# rectifiing.net
KiCad netlist of a schematic drawn in EAGLE
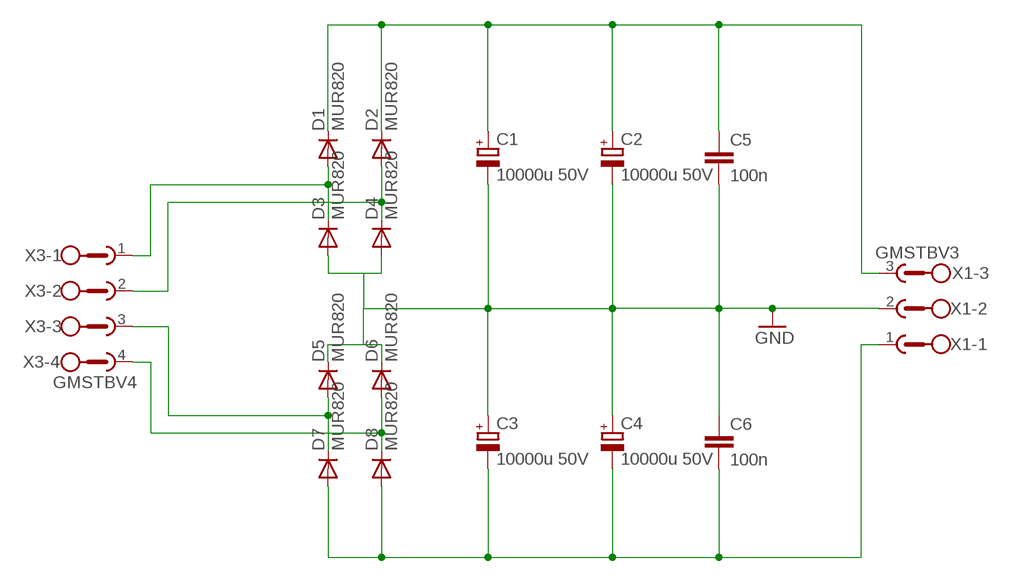
[diagram p0: schematic, sheet 1]

(export (version "E")
  (design (tool "Eeschema 10.0.6"))
  (components
    (comp (ref "C1")
      (value "10000u 50V")
      (footprint "eagle-import:EB30D")
      (libsource (lib "eagle-import") (part "CPOL-EUE10-30"))
    )
    (comp (ref "C2")
      (value "10000u 50V")
      (footprint "eagle-import:EB30D")
      (libsource (lib "eagle-import") (part "CPOL-EUE10-30"))
    )
    (comp (ref "C3")
      (value "10000u 50V")
      (footprint "eagle-import:EB30D")
      (libsource (lib "eagle-import") (part "CPOL-EUE10-30"))
    )
    (comp (ref "C4")
      (value "10000u 50V")
      (footprint "eagle-import:EB30D")
      (libsource (lib "eagle-import") (part "CPOL-EUE10-30"))
    )
    (comp (ref "C5")
      (value "100n")
      (footprint "eagle-import:C075-032X103")
      (libsource (lib "eagle-import") (part "C-EU075-032X103"))
    )
    (comp (ref "C6")
      (value "100n")
      (footprint "eagle-import:C075-032X103")
      (libsource (lib "eagle-import") (part "C-EU075-032X103"))
    )
    (comp (ref "D1")
      (value "MUR820")
      (footprint "eagle-import:TO220ACS")
      (libsource (lib "eagle-import") (part "MUR810"))
    )
    (comp (ref "D2")
      (value "MUR820")
      (footprint "eagle-import:TO220ACS")
      (libsource (lib "eagle-import") (part "MUR810"))
    )
    (comp (ref "D3")
      (value "MUR820")
      (footprint "eagle-import:TO220ACS")
      (libsource (lib "eagle-import") (part "MUR810"))
    )
    (comp (ref "D4")
      (value "MUR820")
      (footprint "eagle-import:TO220ACS")
      (libsource (lib "eagle-import") (part "MUR810"))
    )
    (comp (ref "D5")
      (value "MUR820")
      (footprint "eagle-import:TO220ACS")
      (libsource (lib "eagle-import") (part "MUR810"))
    )
    (comp (ref "D6")
      (value "MUR820")
      (footprint "eagle-import:TO220ACS")
      (libsource (lib "eagle-import") (part "MUR810"))
    )
    (comp (ref "D7")
      (value "MUR820")
      (footprint "eagle-import:TO220ACS")
      (libsource (lib "eagle-import") (part "MUR810"))
    )
    (comp (ref "D8")
      (value "MUR820")
      (footprint "eagle-import:TO220ACS")
      (libsource (lib "eagle-import") (part "MUR810"))
    )
    (comp (ref "X1")
      (value "GMSTBV3")
      (footprint "eagle-import:GMSTBV3")
      (fields (field (name "MPN") "GMSTBVA2,5/3-G-7,62"))
      (libsource (lib "eagle-import") (part "GMSTBV3"))
    )
    (comp (ref "X3")
      (value "GMSTBV4")
      (footprint "eagle-import:GMSTBV4")
      (fields (field (name "MPN") "GMSTBVA2,5/4-G-7,62"))
      (libsource (lib "eagle-import") (part "GMSTBV4"))
    )
  )
  (nets
    (net (code "1") (name "GND") (class "Default")
      (node (ref "C1") (pin "-") (pinfunction "-_-") (pintype "passive"))
      (node (ref "C2") (pin "-") (pinfunction "-_-") (pintype "passive"))
      (node (ref "C3") (pin "+") (pinfunction "+_+") (pintype "passive"))
      (node (ref "C4") (pin "+") (pinfunction "+_+") (pintype "passive"))
      (node (ref "C5") (pin "2") (pinfunction "2_2") (pintype "passive"))
      (node (ref "C6") (pin "1") (pinfunction "1_1") (pintype "passive"))
      (node (ref "D3") (pin "A") (pinfunction "A_A") (pintype "passive"))
      (node (ref "D4") (pin "A") (pinfunction "A_A") (pintype "passive"))
      (node (ref "D5") (pin "C") (pinfunction "C_C") (pintype "passive"))
      (node (ref "D6") (pin "C") (pinfunction "C_C") (pintype "passive"))
      (node (ref "X1") (pin "2") (pinfunction "1_2") (pintype "passive"))
    )
    (net (code "2") (name "Net-(C3-Pad-)") (class "Default")
      (node (ref "C3") (pin "-") (pinfunction "-_-") (pintype "passive"))
      (node (ref "C4") (pin "-") (pinfunction "-_-") (pintype "passive"))
      (node (ref "C6") (pin "2") (pinfunction "2_2") (pintype "passive"))
      (node (ref "D7") (pin "A") (pinfunction "A_A") (pintype "passive"))
      (node (ref "D8") (pin "A") (pinfunction "A_A") (pintype "passive"))
      (node (ref "X1") (pin "1") (pinfunction "1_1") (pintype "passive"))
    )
    (net (code "3") (name "Net-(D1-PadA)") (class "Default")
      (node (ref "D1") (pin "A") (pinfunction "A_A") (pintype "passive"))
      (node (ref "D3") (pin "C") (pinfunction "C_C") (pintype "passive"))
      (node (ref "X3") (pin "1") (pinfunction "1_1") (pintype "passive"))
    )
    (net (code "4") (name "Net-(X1C-1)") (class "Default")
      (node (ref "C1") (pin "+") (pinfunction "+_+") (pintype "passive"))
      (node (ref "C2") (pin "+") (pinfunction "+_+") (pintype "passive"))
      (node (ref "C5") (pin "1") (pinfunction "1_1") (pintype "passive"))
      (node (ref "D1") (pin "C") (pinfunction "C_C") (pintype "passive"))
      (node (ref "D2") (pin "C") (pinfunction "C_C") (pintype "passive"))
      (node (ref "X1") (pin "3") (pinfunction "1_3") (pintype "passive"))
    )
    (net (code "5") (name "Net-(X3B-1)") (class "Default")
      (node (ref "D2") (pin "A") (pinfunction "A_A") (pintype "passive"))
      (node (ref "D4") (pin "C") (pinfunction "C_C") (pintype "passive"))
      (node (ref "X3") (pin "2") (pinfunction "1_2") (pintype "passive"))
    )
    (net (code "6") (name "Net-(X3C-1)") (class "Default")
      (node (ref "D5") (pin "A") (pinfunction "A_A") (pintype "passive"))
      (node (ref "D7") (pin "C") (pinfunction "C_C") (pintype "passive"))
      (node (ref "X3") (pin "3") (pinfunction "1_3") (pintype "passive"))
    )
    (net (code "7") (name "Net-(X3D-1)") (class "Default")
      (node (ref "D6") (pin "A") (pinfunction "A_A") (pintype "passive"))
      (node (ref "D8") (pin "C") (pinfunction "C_C") (pintype "passive"))
      (node (ref "X3") (pin "4") (pinfunction "1_4") (pintype "passive"))
    )
  )
)
